# Charger_LM317.net
KiCad netlist of a schematic drawn in EAGLE
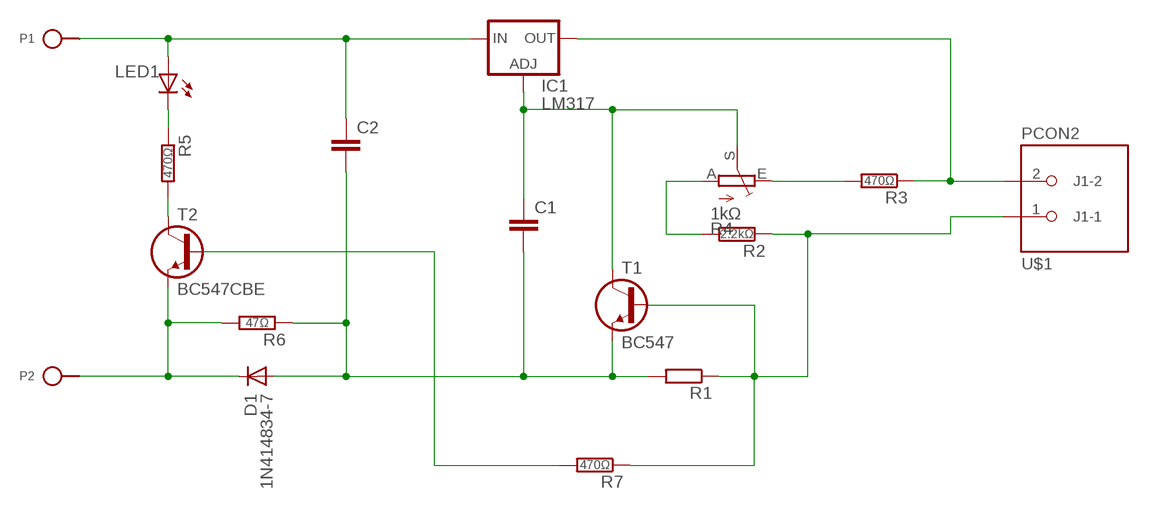
[diagram p0: schematic, sheet 1]

(export (version "E")
  (design (tool "Eeschema 10.0.6"))
  (components
    (comp (ref "C1")
      (value "C050-020X036")
      (footprint "eagle-import:C050-020X036")
      (libsource (lib "eagle-import") (part "C050-020X036"))
    )
    (comp (ref "C2")
      (value "C050-020X036")
      (footprint "eagle-import:C050-020X036")
      (libsource (lib "eagle-import") (part "C050-020X036"))
    )
    (comp (ref "D1")
      (value "1N414834-7")
      (footprint "eagle-import:DO34-7")
      (libsource (lib "eagle-import") (part "1N414834-7"))
    )
    (comp (ref "IC1")
      (value "LM317")
      (footprint "eagle-import:317TL")
      (libsource (lib "eagle-import") (part "LM317TL"))
    )
    (comp (ref "LED1")
      (value "LED5MM")
      (footprint "eagle-import:LED5MM")
      (libsource (lib "eagle-import") (part "LED5MM"))
    )
    (comp (ref "P1")
      (value "+")
      (footprint "eagle-import:SPAD")
      (libsource (lib "eagle-import") (part "SPAD"))
    )
    (comp (ref "P2")
      (value "-")
      (footprint "eagle-import:SPAD")
      (libsource (lib "eagle-import") (part "SPAD"))
    )
    (comp (ref "R1")
      (value "R0207/7")
      (footprint "eagle-import:0207_7")
      (libsource (lib "eagle-import") (part "R0207/7"))
    )
    (comp (ref "R2")
      (value "2.2kΩ")
      (footprint "eagle-import:0202_5")
      (libsource (lib "eagle-import") (part "R0202/5"))
    )
    (comp (ref "R3")
      (value "470Ω")
      (footprint "eagle-import:0202_7")
      (libsource (lib "eagle-import") (part "R0202/7"))
    )
    (comp (ref "R4")
      (value "1kΩ")
      (footprint "eagle-import:B25P")
      (libsource (lib "eagle-import") (part "TRIM_EU-B25P"))
    )
    (comp (ref "R5")
      (value "470Ω")
      (footprint "eagle-import:0202_7")
      (libsource (lib "eagle-import") (part "R0202/7"))
    )
    (comp (ref "R6")
      (value "47Ω")
      (footprint "eagle-import:0202_7")
      (libsource (lib "eagle-import") (part "R0202/7"))
    )
    (comp (ref "R7")
      (value "470Ω")
      (footprint "eagle-import:0202_7")
      (libsource (lib "eagle-import") (part "R0202/7"))
    )
    (comp (ref "T1")
      (value "BC547")
      (footprint "eagle-import:TO92-CBE")
      (libsource (lib "eagle-import") (part "BC547CBE"))
    )
    (comp (ref "T2")
      (value "BC547CBE")
      (footprint "eagle-import:TO92-CBE")
      (libsource (lib "eagle-import") (part "BC547CBE"))
    )
    (comp (ref "U$1")
      (value "PCON2")
      (footprint "eagle-import:CON-2PIN")
      (libsource (lib "eagle-import") (part "PCON2"))
    )
  )
  (nets
    (net (code "1") (name "Net-(C1-Pad2)") (class "Default")
      (node (ref "C1") (pin "2") (pinfunction "2_2") (pintype "passive"))
      (node (ref "C2") (pin "2") (pinfunction "2_2") (pintype "passive"))
      (node (ref "D1") (pin "A") (pinfunction "A_A") (pintype "passive"))
      (node (ref "R1") (pin "2") (pinfunction "2_2") (pintype "passive"))
      (node (ref "R6") (pin "1") (pinfunction "1_1") (pintype "passive"))
      (node (ref "T1") (pin "E") (pinfunction "E_E") (pintype "passive"))
    )
    (net (code "2") (name "Net-(IC1-ADJ)") (class "Default")
      (node (ref "C1") (pin "1") (pinfunction "1_1") (pintype "passive"))
      (node (ref "IC1") (pin "1") (pinfunction "ADJ_1") (pintype "input"))
      (node (ref "R4") (pin "S") (pinfunction "S_S") (pintype "passive"))
      (node (ref "T1") (pin "C") (pinfunction "C_C") (pintype "passive"))
    )
    (net (code "3") (name "Net-(IC1-IN)") (class "Default")
      (node (ref "C2") (pin "1") (pinfunction "1_1") (pintype "passive"))
      (node (ref "IC1") (pin "3") (pinfunction "IN_3") (pintype "input"))
      (node (ref "LED1") (pin "A") (pinfunction "A_A") (pintype "passive"))
      (node (ref "P1") (pin "1") (pinfunction "P$1_1") (pintype "bidirectional"))
    )
    (net (code "4") (name "Net-(IC1-OUT)") (class "Default")
      (node (ref "IC1") (pin "2") (pinfunction "OUT_2") (pintype "passive"))
      (node (ref "R3") (pin "1") (pinfunction "1_1") (pintype "passive"))
      (node (ref "U$1") (pin "2") (pinfunction "J1-2_2") (pintype "passive"))
    )
    (net (code "5") (name "Net-(LED1-C)") (class "Default")
      (node (ref "LED1") (pin "K") (pinfunction "C_K") (pintype "passive"))
      (node (ref "R5") (pin "1") (pinfunction "1_1") (pintype "passive"))
    )
    (net (code "6") (name "Net-(P2-P$1)") (class "Default")
      (node (ref "D1") (pin "C") (pinfunction "C_C") (pintype "passive"))
      (node (ref "P2") (pin "1") (pinfunction "P$1_1") (pintype "bidirectional"))
      (node (ref "R6") (pin "2") (pinfunction "2_2") (pintype "passive"))
      (node (ref "T2") (pin "E") (pinfunction "E_E") (pintype "passive"))
    )
    (net (code "7") (name "Net-(R2-Pad2)") (class "Default")
      (node (ref "R2") (pin "2") (pinfunction "2_2") (pintype "passive"))
      (node (ref "R4") (pin "A") (pinfunction "A_A") (pintype "passive"))
    )
    (net (code "8") (name "Net-(R3-Pad2)") (class "Default")
      (node (ref "R3") (pin "2") (pinfunction "2_2") (pintype "passive"))
      (node (ref "R4") (pin "E") (pinfunction "E_E") (pintype "passive"))
    )
    (net (code "9") (name "Net-(R5-Pad2)") (class "Default")
      (node (ref "R5") (pin "2") (pinfunction "2_2") (pintype "passive"))
      (node (ref "T2") (pin "C") (pinfunction "C_C") (pintype "passive"))
    )
    (net (code "10") (name "Net-(R7-Pad2)") (class "Default")
      (node (ref "R7") (pin "2") (pinfunction "2_2") (pintype "passive"))
      (node (ref "T2") (pin "B") (pinfunction "B_B") (pintype "passive"))
    )
    (net (code "11") (name "Net-(U$1-J1-1)") (class "Default")
      (node (ref "R1") (pin "1") (pinfunction "1_1") (pintype "passive"))
      (node (ref "R2") (pin "1") (pinfunction "1_1") (pintype "passive"))
      (node (ref "R7") (pin "1") (pinfunction "1_1") (pintype "passive"))
      (node (ref "T1") (pin "B") (pinfunction "B_B") (pintype "passive"))
      (node (ref "U$1") (pin "1") (pinfunction "J1-1_1") (pintype "passive"))
    )
  )
)
